# pic500.net
KiCad netlist of a schematic drawn in EAGLE
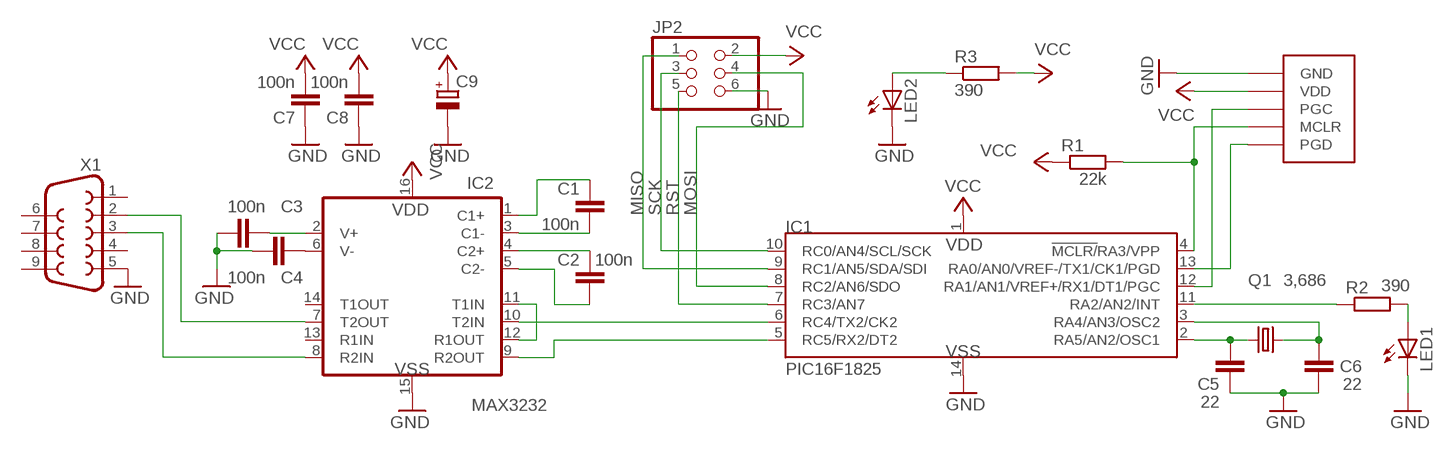
[diagram p0: schematic, sheet 1]

(export (version "E")
  (design (tool "Eeschema 10.0.6"))
  (components
    (comp (ref "C1")
      (value "100n")
      (footprint "eagle-import:C025-025X050")
      (libsource (lib "eagle-import") (part "C-EU025-025X050"))
    )
    (comp (ref "C2")
      (value "100n")
      (footprint "eagle-import:C025-025X050")
      (libsource (lib "eagle-import") (part "C-EU025-025X050"))
    )
    (comp (ref "C3")
      (value "100n")
      (footprint "eagle-import:C025-025X050")
      (libsource (lib "eagle-import") (part "C-EU025-025X050"))
    )
    (comp (ref "C4")
      (value "100n")
      (footprint "eagle-import:C025-025X050")
      (libsource (lib "eagle-import") (part "C-EU025-025X050"))
    )
    (comp (ref "C5")
      (value "22")
      (footprint "eagle-import:C025-025X050")
      (libsource (lib "eagle-import") (part "C-EU025-025X050"))
    )
    (comp (ref "C6")
      (value "22")
      (footprint "eagle-import:C025-025X050")
      (libsource (lib "eagle-import") (part "C-EU025-025X050"))
    )
    (comp (ref "C7")
      (value "100n")
      (footprint "eagle-import:C025-025X050")
      (libsource (lib "eagle-import") (part "C-EU025-025X050"))
    )
    (comp (ref "C8")
      (value "100n")
      (footprint "eagle-import:C025-025X050")
      (libsource (lib "eagle-import") (part "C-EU025-025X050"))
    )
    (comp (ref "C9")
      (value "CPOL-EUE2-5")
      (footprint "eagle-import:E2-5")
      (libsource (lib "eagle-import") (part "CPOL-EUE2-5"))
    )
    (comp (ref "IC1")
      (value "PIC16F1825")
      (footprint "eagle-import:DIL14")
      (libsource (lib "eagle-import") (part "PIC16F1824"))
    )
    (comp (ref "IC2")
      (value "MAX3232")
      (footprint "eagle-import:DIL16")
      (libsource (lib "eagle-import") (part "MAX3232"))
    )
    (comp (ref "JP2")
      (value "PINHD-2X03_2.54")
      (footprint "eagle-import:2X03")
      (libsource (lib "eagle-import") (part "PINHD-2X03_2.54"))
    )
    (comp (ref "LED1")
      (value "LED3MM")
      (footprint "eagle-import:LED3MM")
      (libsource (lib "eagle-import") (part "LED3MM"))
    )
    (comp (ref "LED2")
      (value "LED3MM")
      (footprint "eagle-import:LED3MM")
      (libsource (lib "eagle-import") (part "LED3MM"))
    )
    (comp (ref "Q1")
      (value "3,686")
      (footprint "eagle-import:HC49_S")
      (libsource (lib "eagle-import") (part "CRYSTALHC49S"))
    )
    (comp (ref "R1")
      (value "22k")
      (footprint "eagle-import:0207_10")
      (libsource (lib "eagle-import") (part "R-EU_0207/10"))
    )
    (comp (ref "R2")
      (value "390")
      (footprint "eagle-import:0207_10")
      (libsource (lib "eagle-import") (part "R-EU_0207/10"))
    )
    (comp (ref "R3")
      (value "390")
      (footprint "eagle-import:0207_10")
      (libsource (lib "eagle-import") (part "R-EU_0207/10"))
    )
    (comp (ref "U$1")
      (value "PROGHEAD_254")
      (footprint "eagle-import:PROGHEAD_254")
      (libsource (lib "eagle-import") (part "PROGHEAD_254"))
    )
    (comp (ref "X1")
      (value "F09HP")
      (footprint "eagle-import:F09HP")
      (libsource (lib "eagle-import") (part "F09HP"))
    )
  )
  (nets
    (net (code "1") (name "/MISO") (class "Default")
      (node (ref "IC1") (pin "9") (pinfunction "RC1/AN5/SDA/SDI_9") (pintype "bidirectional"))
      (node (ref "JP2") (pin "1") (pinfunction "1_1") (pintype "passive"))
    )
    (net (code "2") (name "/MOSI") (class "Default")
      (node (ref "IC1") (pin "8") (pinfunction "RC2/AN6/SDO_8") (pintype "bidirectional"))
      (node (ref "JP2") (pin "4") (pinfunction "4_4") (pintype "passive"))
    )
    (net (code "3") (name "/RST") (class "Default")
      (node (ref "IC1") (pin "7") (pinfunction "RC3/AN7_7") (pintype "bidirectional"))
      (node (ref "JP2") (pin "5") (pinfunction "5_5") (pintype "passive"))
    )
    (net (code "4") (name "/SCK") (class "Default")
      (node (ref "IC1") (pin "10") (pinfunction "RC0/AN4/SCL/SCK_10") (pintype "bidirectional"))
      (node (ref "JP2") (pin "3") (pinfunction "3_3") (pintype "passive"))
    )
    (net (code "5") (name "GND") (class "Default")
      (node (ref "C3") (pin "2") (pinfunction "2_2") (pintype "passive"))
      (node (ref "C4") (pin "2") (pinfunction "2_2") (pintype "passive"))
      (node (ref "C5") (pin "1") (pinfunction "1_1") (pintype "passive"))
      (node (ref "C6") (pin "1") (pinfunction "1_1") (pintype "passive"))
      (node (ref "C7") (pin "1") (pinfunction "1_1") (pintype "passive"))
      (node (ref "C8") (pin "1") (pinfunction "1_1") (pintype "passive"))
      (node (ref "C9") (pin "-") (pinfunction "-_-") (pintype "passive"))
      (node (ref "IC1") (pin "14") (pinfunction "VSS_14") (pintype "power_in"))
      (node (ref "IC2") (pin "15") (pinfunction "VSS_15") (pintype "power_in"))
      (node (ref "JP2") (pin "6") (pinfunction "6_6") (pintype "passive"))
      (node (ref "LED1") (pin "K") (pinfunction "C_K") (pintype "passive"))
      (node (ref "LED2") (pin "K") (pinfunction "C_K") (pintype "passive"))
      (node (ref "U$1") (pin "GND") (pinfunction "GND_GND") (pintype "bidirectional"))
      (node (ref "X1") (pin "5") (pinfunction "5_5") (pintype "passive"))
    )
    (net (code "6") (name "Net-(IC1-RA0{slash}AN0{slash}VREF-{slash}TX1{slash}CK1{slash}PGD)") (class "Default")
      (node (ref "IC1") (pin "13") (pinfunction "RA0/AN0/VREF-/TX1/CK1/PGD_13") (pintype "bidirectional"))
      (node (ref "U$1") (pin "PGD") (pinfunction "PGD_PGD") (pintype "bidirectional"))
    )
    (net (code "7") (name "Net-(IC1-RA1{slash}AN1{slash}VREF+{slash}RX1{slash}DT1{slash}PGC)") (class "Default")
      (node (ref "IC1") (pin "12") (pinfunction "RA1/AN1/VREF+/RX1/DT1/PGC_12") (pintype "bidirectional"))
      (node (ref "U$1") (pin "PGC") (pinfunction "PGC_PGC") (pintype "bidirectional"))
    )
    (net (code "8") (name "Net-(IC1-RA2{slash}AN2{slash}INT)") (class "Default")
      (node (ref "IC1") (pin "11") (pinfunction "RA2/AN2/INT_11") (pintype "bidirectional"))
      (node (ref "R2") (pin "1") (pinfunction "1_1") (pintype "passive"))
    )
    (net (code "9") (name "Net-(IC1-RA4{slash}AN3{slash}OSC2)") (class "Default")
      (node (ref "C6") (pin "2") (pinfunction "2_2") (pintype "passive"))
      (node (ref "IC1") (pin "3") (pinfunction "RA4/AN3/OSC2_3") (pintype "bidirectional"))
      (node (ref "Q1") (pin "2") (pinfunction "2_2") (pintype "passive"))
    )
    (net (code "10") (name "Net-(IC1-RA5{slash}AN2{slash}OSC1)") (class "Default")
      (node (ref "C5") (pin "2") (pinfunction "2_2") (pintype "passive"))
      (node (ref "IC1") (pin "2") (pinfunction "RA5/AN2/OSC1_2") (pintype "bidirectional"))
      (node (ref "Q1") (pin "1") (pinfunction "1_1") (pintype "passive"))
    )
    (net (code "11") (name "Net-(IC1-RC4{slash}TX2{slash}CK2)") (class "Default")
      (node (ref "IC1") (pin "6") (pinfunction "RC4/TX2/CK2_6") (pintype "bidirectional"))
      (node (ref "IC2") (pin "10") (pinfunction "T2IN_10") (pintype "input"))
    )
    (net (code "12") (name "Net-(IC1-RC5{slash}RX2{slash}DT2)") (class "Default")
      (node (ref "IC1") (pin "5") (pinfunction "RC5/RX2/DT2_5") (pintype "bidirectional"))
      (node (ref "IC2") (pin "9") (pinfunction "R2OUT_9") (pintype "input"))
    )
    (net (code "13") (name "Net-(IC1-~{MCLR{slash}}RA3{slash}VPP)") (class "Default")
      (node (ref "IC1") (pin "4") (pinfunction "~{MCLR/}RA3/VPP_4") (pintype "bidirectional"))
      (node (ref "R1") (pin "2") (pinfunction "2_2") (pintype "passive"))
      (node (ref "U$1") (pin "MCLR") (pinfunction "MCLR_MCLR") (pintype "bidirectional"))
    )
    (net (code "14") (name "Net-(IC2-C1+)") (class "Default")
      (node (ref "C1") (pin "1") (pinfunction "1_1") (pintype "passive"))
      (node (ref "IC2") (pin "1") (pinfunction "C1+_1") (pintype "bidirectional"))
    )
    (net (code "15") (name "Net-(IC2-C1-)") (class "Default")
      (node (ref "C1") (pin "2") (pinfunction "2_2") (pintype "passive"))
      (node (ref "IC2") (pin "3") (pinfunction "C1-_3") (pintype "bidirectional"))
    )
    (net (code "16") (name "Net-(IC2-C2+)") (class "Default")
      (node (ref "C2") (pin "1") (pinfunction "1_1") (pintype "passive"))
      (node (ref "IC2") (pin "4") (pinfunction "C2+_4") (pintype "bidirectional"))
    )
    (net (code "17") (name "Net-(IC2-C2-)") (class "Default")
      (node (ref "C2") (pin "2") (pinfunction "2_2") (pintype "passive"))
      (node (ref "IC2") (pin "5") (pinfunction "C2-_5") (pintype "bidirectional"))
    )
    (net (code "18") (name "Net-(IC2-R1OUT)") (class "Default")
      (node (ref "IC2") (pin "11") (pinfunction "T1IN_11") (pintype "input"))
      (node (ref "IC2") (pin "12") (pinfunction "R1OUT_12") (pintype "input"))
    )
    (net (code "19") (name "Net-(IC2-R2IN)") (class "Default")
      (node (ref "IC2") (pin "8") (pinfunction "R2IN_8") (pintype "output"))
      (node (ref "X1") (pin "3") (pinfunction "3_3") (pintype "passive"))
    )
    (net (code "20") (name "Net-(IC2-T2OUT)") (class "Default")
      (node (ref "IC2") (pin "7") (pinfunction "T2OUT_7") (pintype "output"))
      (node (ref "X1") (pin "2") (pinfunction "2_2") (pintype "passive"))
    )
    (net (code "21") (name "Net-(IC2-V+)") (class "Default")
      (node (ref "C3") (pin "1") (pinfunction "1_1") (pintype "passive"))
      (node (ref "IC2") (pin "2") (pinfunction "V+_2") (pintype "bidirectional"))
    )
    (net (code "22") (name "Net-(IC2-V-)") (class "Default")
      (node (ref "C4") (pin "1") (pinfunction "1_1") (pintype "passive"))
      (node (ref "IC2") (pin "6") (pinfunction "V-_6") (pintype "bidirectional"))
    )
    (net (code "23") (name "Net-(LED1-PadA)") (class "Default")
      (node (ref "LED1") (pin "A") (pinfunction "A_A") (pintype "passive"))
      (node (ref "R2") (pin "2") (pinfunction "2_2") (pintype "passive"))
    )
    (net (code "24") (name "Net-(LED2-PadA)") (class "Default")
      (node (ref "LED2") (pin "A") (pinfunction "A_A") (pintype "passive"))
      (node (ref "R3") (pin "1") (pinfunction "1_1") (pintype "passive"))
    )
    (net (code "25") (name "VCC") (class "Default")
      (node (ref "C7") (pin "2") (pinfunction "2_2") (pintype "passive"))
      (node (ref "C8") (pin "2") (pinfunction "2_2") (pintype "passive"))
      (node (ref "C9") (pin "+") (pinfunction "+_+") (pintype "passive"))
      (node (ref "IC1") (pin "1") (pinfunction "VDD_1") (pintype "power_in"))
      (node (ref "IC2") (pin "16") (pinfunction "VDD_16") (pintype "power_in"))
      (node (ref "JP2") (pin "2") (pinfunction "2_2") (pintype "passive"))
      (node (ref "R1") (pin "1") (pinfunction "1_1") (pintype "passive"))
      (node (ref "R3") (pin "2") (pinfunction "2_2") (pintype "passive"))
      (node (ref "U$1") (pin "VDD") (pinfunction "VDD_VDD") (pintype "bidirectional"))
    )
    (net (code "26") (name "unconnected-(IC2-R1IN-Pad13)") (class "Default")
      (node (ref "IC2") (pin "13") (pinfunction "R1IN_13") (pintype "output"))
    )
    (net (code "27") (name "unconnected-(IC2-T1OUT-Pad14)") (class "Default")
      (node (ref "IC2") (pin "14") (pinfunction "T1OUT_14") (pintype "output"))
    )
    (net (code "28") (name "unconnected-(X1-Pad1)") (class "Default")
      (node (ref "X1") (pin "1") (pinfunction "1_1") (pintype "passive"))
    )
    (net (code "29") (name "unconnected-(X1-Pad4)") (class "Default")
      (node (ref "X1") (pin "4") (pinfunction "4_4") (pintype "passive"))
    )
    (net (code "30") (name "unconnected-(X1-Pad6)") (class "Default")
      (node (ref "X1") (pin "6") (pinfunction "6_6") (pintype "passive"))
    )
    (net (code "31") (name "unconnected-(X1-Pad7)") (class "Default")
      (node (ref "X1") (pin "7") (pinfunction "7_7") (pintype "passive"))
    )
    (net (code "32") (name "unconnected-(X1-Pad8)") (class "Default")
      (node (ref "X1") (pin "8") (pinfunction "8_8") (pintype "passive"))
    )
    (net (code "33") (name "unconnected-(X1-Pad9)") (class "Default")
      (node (ref "X1") (pin "9") (pinfunction "9_9") (pintype "passive"))
    )
  )
)
